# Schematic.net
KiCad netlist of a schematic drawn in EasyEDA
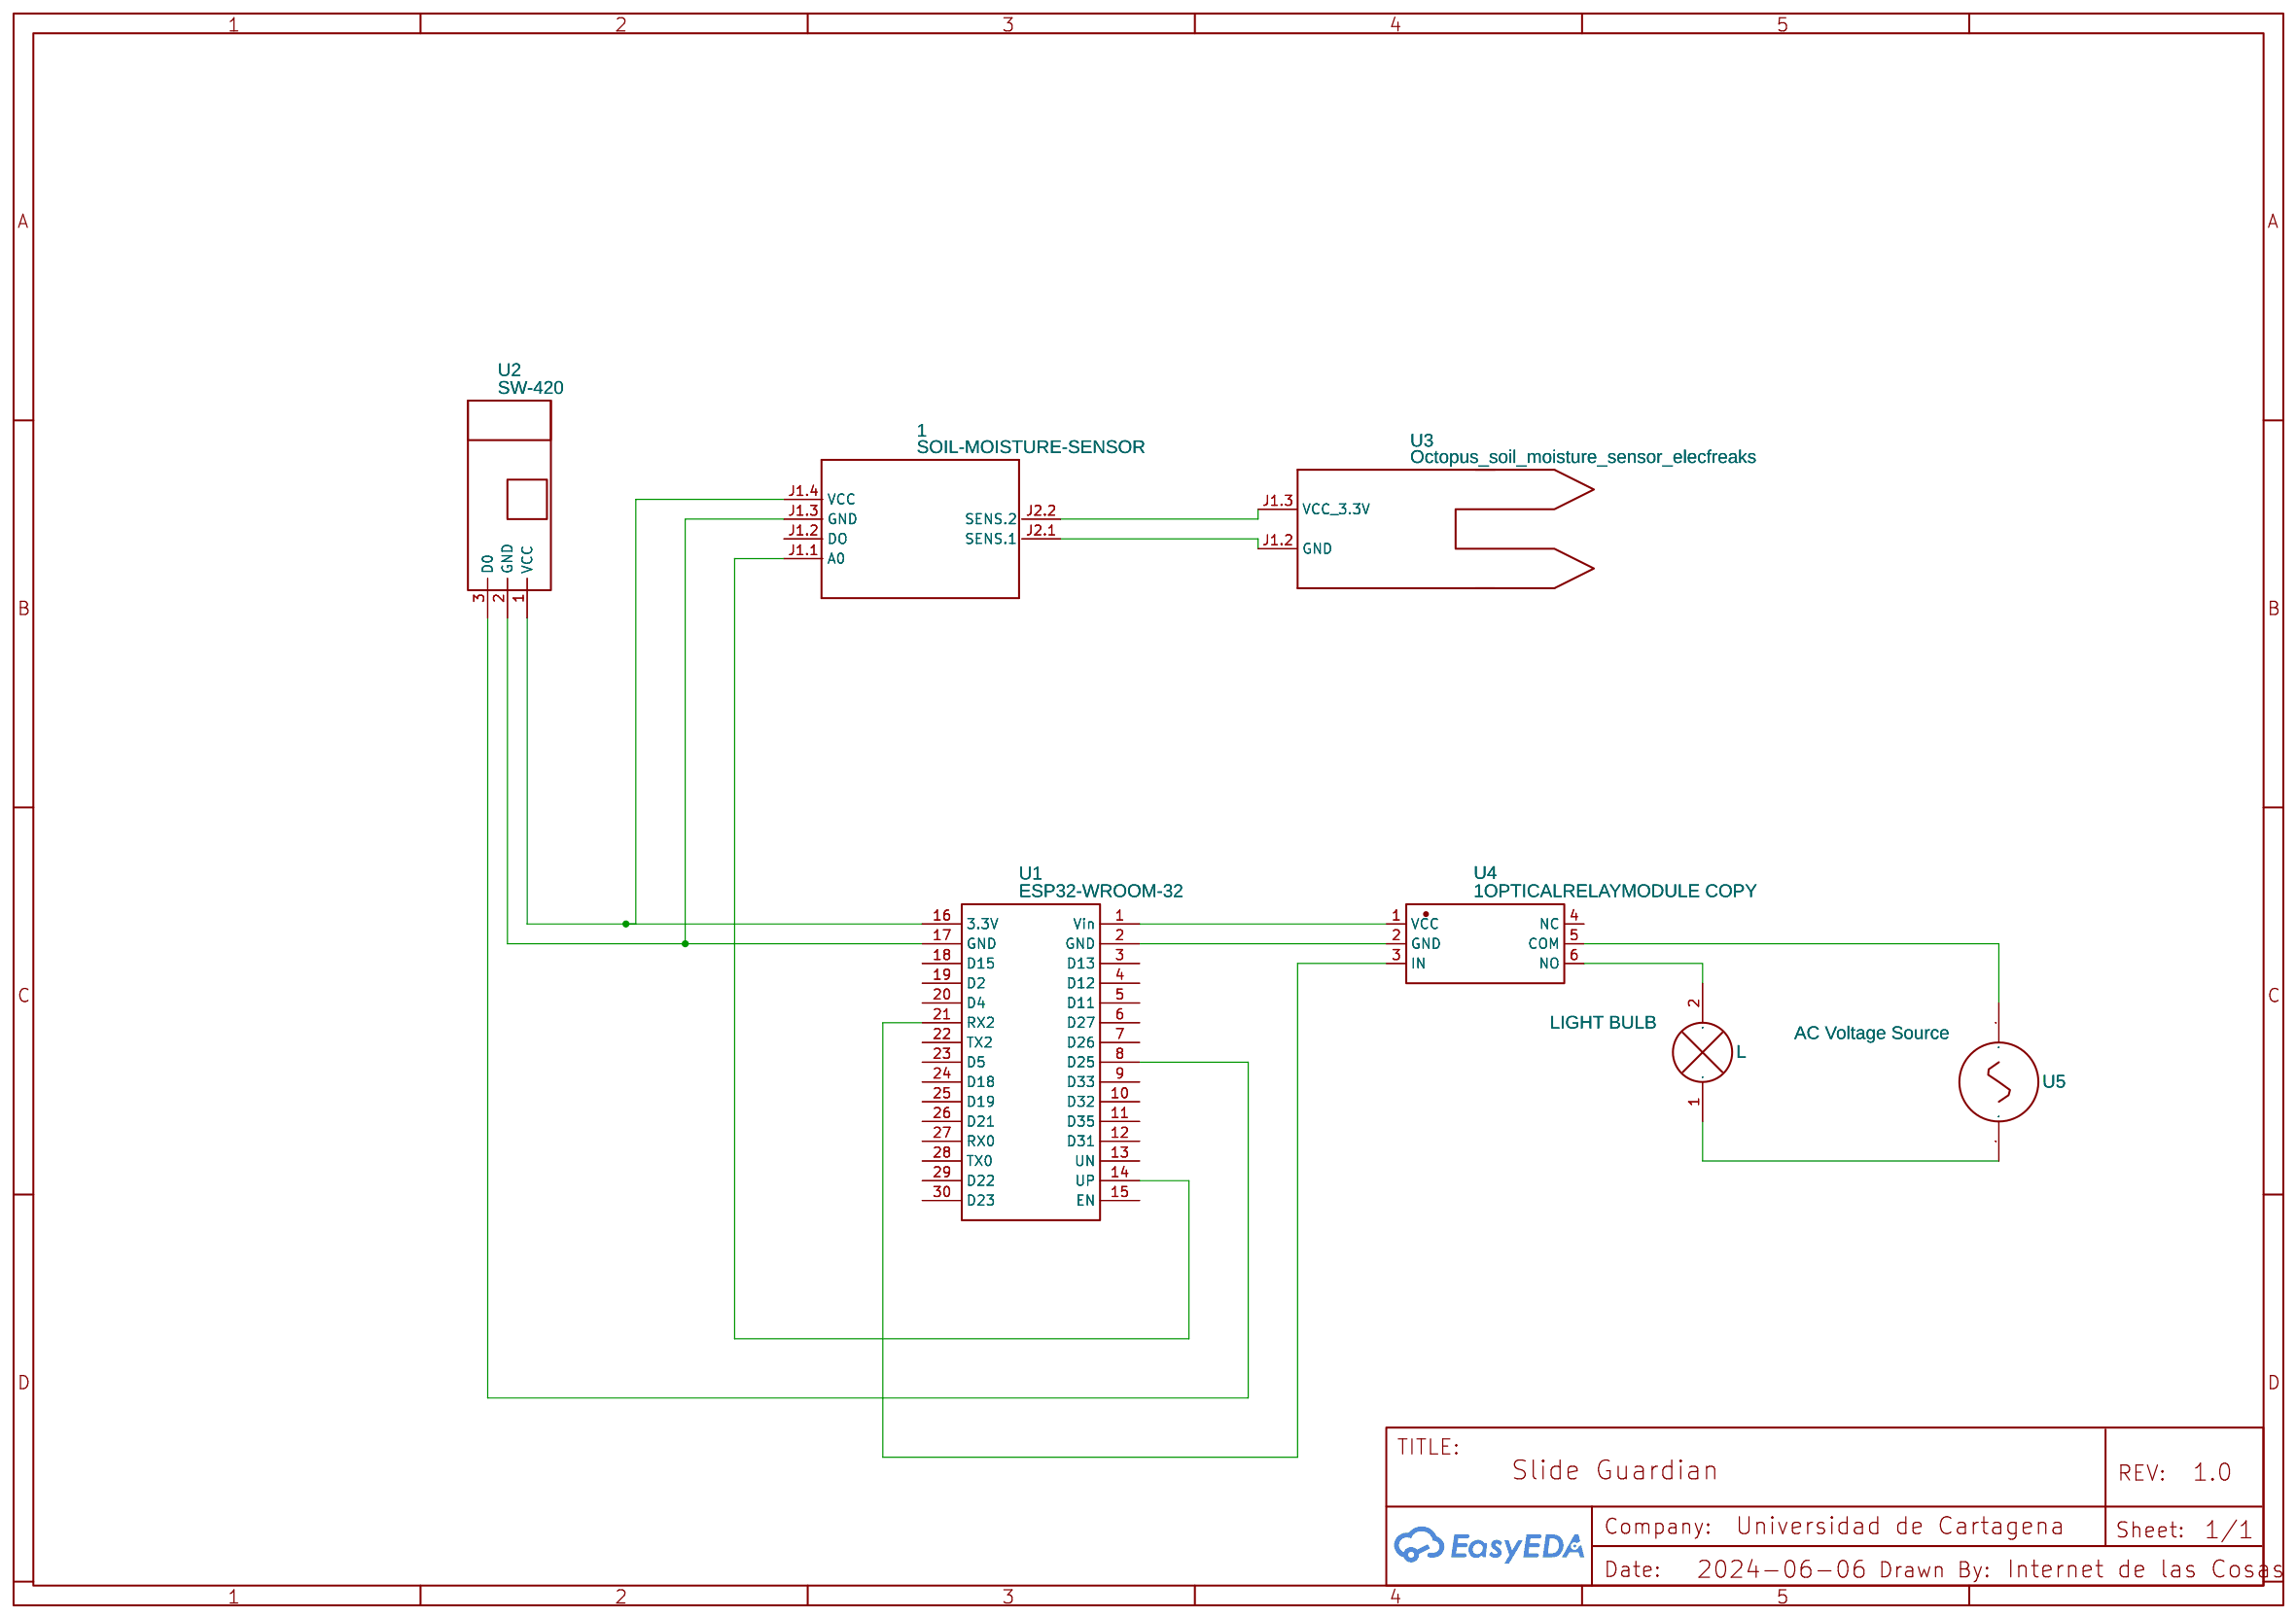
[diagram p0: schematic sheet]

(export (version "E")
  (design (tool "Eeschema 10.0.6"))
  (components
    (comp (ref "1") (value "SOIL-MOISTURE-SENSOR") (libsource (lib "") (part "SOIL-MOISTURE-SENSOR")))
    (comp (ref "L") (value "LIGHT BULB") (libsource (lib "") (part "LIGHT BULB")))
    (comp (ref "U1")
      (value "ESP32-WROOM-32")
      (fields (field (name "Manufacturer") "Espressif"))
      (libsource (lib "") (part "ESP32-WROOM-32"))
    )
    (comp (ref "U2") (value "SW-420") (libsource (lib "") (part "SW-420")))
    (comp (ref "U3")
      (value "Octopus_soil_moisture_sensor_elecfreaks")
      (libsource (lib "") (part "Octopus_soil_moisture_sensor_elecfreaks"))
    )
    (comp (ref "U4")
      (value "1OPTICALRELAYMODULE COPY")
      (libsource (lib "") (part "1OPTICALRELAYMODULE COPY"))
    )
    (comp (ref "U5") (value "AC Voltage Source") (libsource (lib "") (part "AC Voltage Source")))
  )
  (nets
    (net (code "1") (name "Net-(1-A0)") (class "Default")
      (node (ref "1") (pin "J1.1") (pinfunction "A0_J1.1") (pintype "bidirectional"))
      (node (ref "U1") (pin "14") (pinfunction "UP_14") (pintype "unspecified"))
    )
    (net (code "2") (name "Net-(1-GND)") (class "Default")
      (node (ref "1") (pin "J1.3") (pinfunction "GND_J1.3") (pintype "bidirectional"))
      (node (ref "U1") (pin "17") (pinfunction "GND_17") (pintype "unspecified"))
      (node (ref "U2") (pin "2") (pinfunction "GND_2") (pintype "unspecified"))
    )
    (net (code "3") (name "Net-(1-SENS.1)") (class "Default")
      (node (ref "1") (pin "J2.1") (pinfunction "SENS.1_J2.1") (pintype "bidirectional"))
      (node (ref "U3") (pin "J1.2") (pinfunction "GND_J1.2") (pintype "passive"))
    )
    (net (code "4") (name "Net-(1-SENS.2)") (class "Default")
      (node (ref "1") (pin "J2.2") (pinfunction "SENS.2_J2.2") (pintype "bidirectional"))
      (node (ref "U3") (pin "J1.3") (pinfunction "VCC_3.3V_J1.3") (pintype "passive"))
    )
    (net (code "5") (name "Net-(1-VCC)") (class "Default")
      (node (ref "1") (pin "J1.4") (pinfunction "VCC_J1.4") (pintype "bidirectional"))
      (node (ref "U1") (pin "16") (pinfunction "3.3V_16") (pintype "unspecified"))
      (node (ref "U2") (pin "1") (pinfunction "VCC_1") (pintype "unspecified"))
    )
    (net (code "6") (name "Net-(L-Pad1)") (class "Default")
      (node (ref "L") (pin "1") (pinfunction "1_1") (pintype "unspecified"))
      (node (ref "U5") (pin "2") (pinfunction "2_2") (pintype "unspecified"))
    )
    (net (code "7") (name "Net-(U1-D25)") (class "Default")
      (node (ref "U1") (pin "8") (pinfunction "D25_8") (pintype "unspecified"))
      (node (ref "U2") (pin "3") (pinfunction "D0_3") (pintype "unspecified"))
    )
    (net (code "8") (name "Net-(U1-RX2)") (class "Default")
      (node (ref "U1") (pin "21") (pinfunction "RX2_21") (pintype "unspecified"))
      (node (ref "U4") (pin "3") (pinfunction "IN_3") (pintype "unspecified"))
    )
    (net (code "9") (name "Net-(U1-Vin)") (class "Default")
      (node (ref "U1") (pin "1") (pinfunction "Vin_1") (pintype "unspecified"))
      (node (ref "U4") (pin "1") (pinfunction "VCC_1") (pintype "unspecified"))
    )
    (net (code "10") (name "Net-(U4-COM)") (class "Default")
      (node (ref "U4") (pin "5") (pinfunction "COM_5") (pintype "unspecified"))
      (node (ref "U5") (pin "1") (pinfunction "1_1") (pintype "unspecified"))
    )
    (net (code "11") (name "Net-(U4-GND)") (class "Default")
      (node (ref "U1") (pin "2") (pinfunction "GND_2") (pintype "unspecified"))
      (node (ref "U4") (pin "2") (pinfunction "GND_2") (pintype "unspecified"))
    )
    (net (code "12") (name "Net-(U4-NO)") (class "Default")
      (node (ref "L") (pin "2") (pinfunction "2_2") (pintype "unspecified"))
      (node (ref "U4") (pin "6") (pinfunction "NO_6") (pintype "unspecified"))
    )
    (net (code "13") (name "unconnected-(1-DO-PadJ1.2)") (class "Default")
      (node (ref "1") (pin "J1.2") (pinfunction "DO_J1.2") (pintype "bidirectional"))
    )
    (net (code "14") (name "unconnected-(U1-D2-Pad19)") (class "Default")
      (node (ref "U1") (pin "19") (pinfunction "D2_19") (pintype "unspecified"))
    )
    (net (code "15") (name "unconnected-(U1-D4-Pad20)") (class "Default")
      (node (ref "U1") (pin "20") (pinfunction "D4_20") (pintype "unspecified"))
    )
    (net (code "16") (name "unconnected-(U1-D5-Pad23)") (class "Default")
      (node (ref "U1") (pin "23") (pinfunction "D5_23") (pintype "unspecified"))
    )
    (net (code "17") (name "unconnected-(U1-D11-Pad5)") (class "Default")
      (node (ref "U1") (pin "5") (pinfunction "D11_5") (pintype "unspecified"))
    )
    (net (code "18") (name "unconnected-(U1-D12-Pad4)") (class "Default")
      (node (ref "U1") (pin "4") (pinfunction "D12_4") (pintype "unspecified"))
    )
    (net (code "19") (name "unconnected-(U1-D13-Pad3)") (class "Default")
      (node (ref "U1") (pin "3") (pinfunction "D13_3") (pintype "unspecified"))
    )
    (net (code "20") (name "unconnected-(U1-D15-Pad18)") (class "Default")
      (node (ref "U1") (pin "18") (pinfunction "D15_18") (pintype "unspecified"))
    )
    (net (code "21") (name "unconnected-(U1-D18-Pad24)") (class "Default")
      (node (ref "U1") (pin "24") (pinfunction "D18_24") (pintype "unspecified"))
    )
    (net (code "22") (name "unconnected-(U1-D19-Pad25)") (class "Default")
      (node (ref "U1") (pin "25") (pinfunction "D19_25") (pintype "unspecified"))
    )
    (net (code "23") (name "unconnected-(U1-D21-Pad26)") (class "Default")
      (node (ref "U1") (pin "26") (pinfunction "D21_26") (pintype "unspecified"))
    )
    (net (code "24") (name "unconnected-(U1-D22-Pad29)") (class "Default")
      (node (ref "U1") (pin "29") (pinfunction "D22_29") (pintype "unspecified"))
    )
    (net (code "25") (name "unconnected-(U1-D23-Pad30)") (class "Default")
      (node (ref "U1") (pin "30") (pinfunction "D23_30") (pintype "unspecified"))
    )
    (net (code "26") (name "unconnected-(U1-D26-Pad7)") (class "Default")
      (node (ref "U1") (pin "7") (pinfunction "D26_7") (pintype "unspecified"))
    )
    (net (code "27") (name "unconnected-(U1-D27-Pad6)") (class "Default")
      (node (ref "U1") (pin "6") (pinfunction "D27_6") (pintype "unspecified"))
    )
    (net (code "28") (name "unconnected-(U1-D31-Pad12)") (class "Default")
      (node (ref "U1") (pin "12") (pinfunction "D31_12") (pintype "unspecified"))
    )
    (net (code "29") (name "unconnected-(U1-D32-Pad10)") (class "Default")
      (node (ref "U1") (pin "10") (pinfunction "D32_10") (pintype "unspecified"))
    )
    (net (code "30") (name "unconnected-(U1-D33-Pad9)") (class "Default")
      (node (ref "U1") (pin "9") (pinfunction "D33_9") (pintype "unspecified"))
    )
    (net (code "31") (name "unconnected-(U1-D35-Pad11)") (class "Default")
      (node (ref "U1") (pin "11") (pinfunction "D35_11") (pintype "unspecified"))
    )
    (net (code "32") (name "unconnected-(U1-EN-Pad15)") (class "Default")
      (node (ref "U1") (pin "15") (pinfunction "EN_15") (pintype "unspecified"))
    )
    (net (code "33") (name "unconnected-(U1-RX0-Pad27)") (class "Default")
      (node (ref "U1") (pin "27") (pinfunction "RX0_27") (pintype "unspecified"))
    )
    (net (code "34") (name "unconnected-(U1-TX0-Pad28)") (class "Default")
      (node (ref "U1") (pin "28") (pinfunction "TX0_28") (pintype "unspecified"))
    )
    (net (code "35") (name "unconnected-(U1-TX2-Pad22)") (class "Default")
      (node (ref "U1") (pin "22") (pinfunction "TX2_22") (pintype "unspecified"))
    )
    (net (code "36") (name "unconnected-(U1-UN-Pad13)") (class "Default")
      (node (ref "U1") (pin "13") (pinfunction "UN_13") (pintype "unspecified"))
    )
    (net (code "37") (name "unconnected-(U4-NC-Pad4)") (class "Default")
      (node (ref "U4") (pin "4") (pinfunction "NC_4") (pintype "unspecified"))
    )
  )
)
